# moisture_sensor_schematic.net
KiCad netlist of a schematic drawn in EAGLE
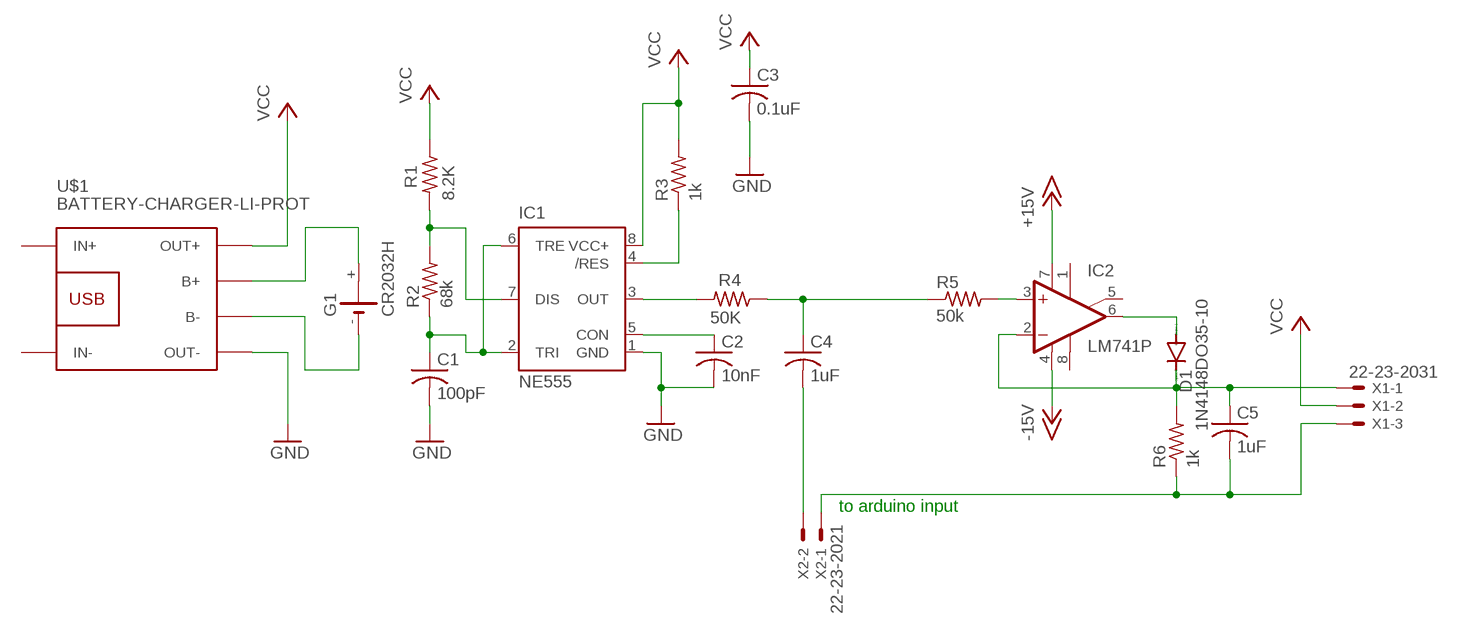
[diagram p0: schematic, sheet 1]

(export (version "E")
  (design (tool "Eeschema 10.0.6"))
  (components
    (comp (ref "C1")
      (value "100pF")
      (footprint "eagle-import:C1206")
      (libsource (lib "eagle-import") (part "C-USC1206"))
    )
    (comp (ref "C2")
      (value "10nF")
      (footprint "eagle-import:C1206")
      (libsource (lib "eagle-import") (part "C-USC1206"))
    )
    (comp (ref "C3")
      (value "0.1uF")
      (footprint "eagle-import:C1206")
      (libsource (lib "eagle-import") (part "C-USC1206"))
    )
    (comp (ref "C4")
      (value "1uF")
      (footprint "eagle-import:C1206")
      (libsource (lib "eagle-import") (part "C-USC1206"))
    )
    (comp (ref "C5")
      (value "1uF")
      (footprint "eagle-import:C1206")
      (libsource (lib "eagle-import") (part "C-USC1206"))
    )
    (comp (ref "D1")
      (value "1N4148DO35-10")
      (footprint "eagle-import:DO35-10")
      (fields (field (name "SPICEPREFIX") "D"))
      (libsource (lib "eagle-import") (part "1N4148DO35-10"))
    )
    (comp (ref "G1")
      (value "CR2032H")
      (footprint "eagle-import:CR2032H")
      (libsource (lib "eagle-import") (part "CR2032H"))
    )
    (comp (ref "IC1")
      (value "NE555")
      (footprint "eagle-import:DIL-08")
      (fields
        (field (name "MF") "Arrow Electronics")
        (field (name "MPN") "NE555N")
        (field (name "SPICEPREFIX") "X")
      )
      (libsource (lib "eagle-import") (part "NE555"))
    )
    (comp (ref "IC2")
      (value "LM741P")
      (footprint "eagle-import:DIL08")
      (fields (field (name "SPICEPREFIX") "X"))
      (libsource (lib "eagle-import") (part "741PLM"))
    )
    (comp (ref "R1")
      (value "8.2K")
      (footprint "eagle-import:R0603")
      (libsource (lib "eagle-import") (part "R-US_R0603"))
    )
    (comp (ref "R2")
      (value "68k")
      (footprint "eagle-import:R0603")
      (libsource (lib "eagle-import") (part "R-US_R0603"))
    )
    (comp (ref "R3")
      (value "1k")
      (footprint "eagle-import:R0603")
      (libsource (lib "eagle-import") (part "R-US_R0603"))
    )
    (comp (ref "R4")
      (value "50K")
      (footprint "eagle-import:R0603")
      (libsource (lib "eagle-import") (part "R-US_R0603"))
    )
    (comp (ref "R5")
      (value "50k")
      (footprint "eagle-import:R0603")
      (libsource (lib "eagle-import") (part "R-US_R0603"))
    )
    (comp (ref "R6")
      (value "1k")
      (footprint "eagle-import:R0603")
      (libsource (lib "eagle-import") (part "R-US_R0603"))
    )
    (comp (ref "U$1")
      (value "BATTERY-CHARGER-LI-PROT")
      (footprint "eagle-import:BATTERY-CHARGER-LI-PROT")
      (fields (field (name "SPICEPREFIX") "X"))
      (libsource (lib "eagle-import") (part "BATTERY-CHARGER-LI-PROT"))
    )
    (comp (ref "X1")
      (value "22-23-2031")
      (footprint "eagle-import:22-23-2031")
      (fields (field (name "MF") "MOLEX") (field (name "SPICEPREFIX") "X"))
      (libsource (lib "eagle-import") (part "22-23-2031"))
    )
    (comp (ref "X2")
      (value "22-23-2021")
      (footprint "eagle-import:22-23-2021")
      (fields (field (name "MF") "MOLEX") (field (name "SPICEPREFIX") "X"))
      (libsource (lib "eagle-import") (part "22-23-2021"))
    )
  )
  (nets
    (net (code "1") (name "+15V") (class "Default")
      (node (ref "IC2") (pin "7") (pinfunction "V+_7") (pintype "power_in"))
    )
    (net (code "2") (name "-15V") (class "Default")
      (node (ref "IC2") (pin "4") (pinfunction "V-_4") (pintype "power_in"))
    )
    (net (code "3") (name "GND") (class "Default")
      (node (ref "C1") (pin "2") (pinfunction "2_2") (pintype "passive"))
      (node (ref "C2") (pin "2") (pinfunction "2_2") (pintype "passive"))
      (node (ref "C3") (pin "2") (pinfunction "2_2") (pintype "passive"))
      (node (ref "IC1") (pin "1") (pinfunction "GND_1") (pintype "power_in"))
      (node (ref "U$1") (pin "OUT-") (pinfunction "OUT-_OUT-") (pintype "bidirectional"))
    )
    (net (code "4") (name "Net-(C4-Pad1)") (class "Default")
      (node (ref "C4") (pin "1") (pinfunction "1_1") (pintype "passive"))
      (node (ref "R4") (pin "1") (pinfunction "1_1") (pintype "passive"))
      (node (ref "R5") (pin "1") (pinfunction "1_1") (pintype "passive"))
    )
    (net (code "5") (name "Net-(G1-Pad+)") (class "Default")
      (node (ref "G1") (pin "+") (pinfunction "+_+") (pintype "passive"))
      (node (ref "U$1") (pin "B+") (pinfunction "B+_B+") (pintype "bidirectional"))
    )
    (net (code "6") (name "Net-(G1-Pad-)") (class "Default")
      (node (ref "G1") (pin "-") (pinfunction "-_-") (pintype "passive"))
      (node (ref "U$1") (pin "B-") (pinfunction "B-_B-") (pintype "bidirectional"))
    )
    (net (code "7") (name "Net-(IC1-CON)") (class "Default")
      (node (ref "C2") (pin "1") (pinfunction "1_1") (pintype "passive"))
      (node (ref "IC1") (pin "5") (pinfunction "CON_5") (pintype "input"))
    )
    (net (code "8") (name "Net-(IC1-DIS)") (class "Default")
      (node (ref "IC1") (pin "7") (pinfunction "DIS_7") (pintype "input"))
      (node (ref "R1") (pin "2") (pinfunction "2_2") (pintype "passive"))
      (node (ref "R2") (pin "2") (pinfunction "2_2") (pintype "passive"))
    )
    (net (code "9") (name "Net-(IC1-OUT)") (class "Default")
      (node (ref "IC1") (pin "3") (pinfunction "OUT_3") (pintype "output"))
      (node (ref "R4") (pin "2") (pinfunction "2_2") (pintype "passive"))
    )
    (net (code "10") (name "Net-(IC1-TRE)") (class "Default")
      (node (ref "C1") (pin "1") (pinfunction "1_1") (pintype "passive"))
      (node (ref "IC1") (pin "2") (pinfunction "TRI_2") (pintype "input"))
      (node (ref "IC1") (pin "6") (pinfunction "TRE_6") (pintype "input"))
      (node (ref "R2") (pin "1") (pinfunction "1_1") (pintype "passive"))
    )
    (net (code "11") (name "Net-(IC1-{slash}RES)") (class "Default")
      (node (ref "IC1") (pin "4") (pinfunction "/RES_4") (pintype "input"))
      (node (ref "R3") (pin "1") (pinfunction "1_1") (pintype "passive"))
    )
    (net (code "12") (name "Net-(IC2-+IN)") (class "Default")
      (node (ref "IC2") (pin "3") (pinfunction "+IN_3") (pintype "input"))
      (node (ref "R5") (pin "2") (pinfunction "2_2") (pintype "passive"))
    )
    (net (code "13") (name "Net-(IC2--IN)") (class "Default")
      (node (ref "C5") (pin "1") (pinfunction "1_1") (pintype "passive"))
      (node (ref "D1") (pin "C") (pinfunction "C_C") (pintype "passive"))
      (node (ref "IC2") (pin "2") (pinfunction "-IN_2") (pintype "input"))
      (node (ref "R6") (pin "2") (pinfunction "2_2") (pintype "passive"))
      (node (ref "X1") (pin "1") (pinfunction "S_1") (pintype "passive"))
    )
    (net (code "14") (name "Net-(IC2-OUT)") (class "Default")
      (node (ref "D1") (pin "A") (pinfunction "A_A") (pintype "passive"))
      (node (ref "IC2") (pin "6") (pinfunction "OUT_6") (pintype "output"))
    )
    (net (code "15") (name "Net-(X1C-S)") (class "Default")
      (node (ref "C5") (pin "2") (pinfunction "2_2") (pintype "passive"))
      (node (ref "R6") (pin "1") (pinfunction "1_1") (pintype "passive"))
      (node (ref "X1") (pin "3") (pinfunction "S_3") (pintype "passive"))
      (node (ref "X2") (pin "1") (pinfunction "S_1") (pintype "passive"))
    )
    (net (code "16") (name "Net-(X2B-S)") (class "Default")
      (node (ref "C4") (pin "2") (pinfunction "2_2") (pintype "passive"))
      (node (ref "X2") (pin "2") (pinfunction "S_2") (pintype "passive"))
    )
    (net (code "17") (name "VCC") (class "Default")
      (node (ref "C3") (pin "1") (pinfunction "1_1") (pintype "passive"))
      (node (ref "IC1") (pin "8") (pinfunction "VCC+_8") (pintype "power_in"))
      (node (ref "R1") (pin "1") (pinfunction "1_1") (pintype "passive"))
      (node (ref "R3") (pin "2") (pinfunction "2_2") (pintype "passive"))
      (node (ref "U$1") (pin "OUT+") (pinfunction "OUT+_OUT+") (pintype "bidirectional"))
      (node (ref "X1") (pin "2") (pinfunction "S_2") (pintype "passive"))
    )
    (net (code "18") (name "unconnected-(G1-+-Pad+@1)") (class "Default")
      (node (ref "G1") (pin "+@1") (pinfunction "+_+@1") (pintype "passive"))
    )
    (net (code "19") (name "unconnected-(IC2-ON1-Pad1)") (class "Default")
      (node (ref "IC2") (pin "1") (pinfunction "ON1_1") (pintype "passive"))
    )
    (net (code "20") (name "unconnected-(IC2-ON2-Pad5)") (class "Default")
      (node (ref "IC2") (pin "5") (pinfunction "ON2_5") (pintype "passive"))
    )
    (net (code "21") (name "unconnected-(IC2-OPT-Pad8)") (class "Default")
      (node (ref "IC2") (pin "8") (pinfunction "OPT_8") (pintype "passive"))
    )
    (net (code "22") (name "unconnected-(U$1-PadIN+)") (class "Default")
      (node (ref "U$1") (pin "IN+") (pinfunction "IN+_IN+") (pintype "bidirectional"))
    )
    (net (code "23") (name "unconnected-(U$1-PadIN-)") (class "Default")
      (node (ref "U$1") (pin "IN-") (pinfunction "IN-_IN-") (pintype "bidirectional"))
    )
  )
)
